# sterownik_RC.net
KiCad netlist of a schematic drawn in EAGLE
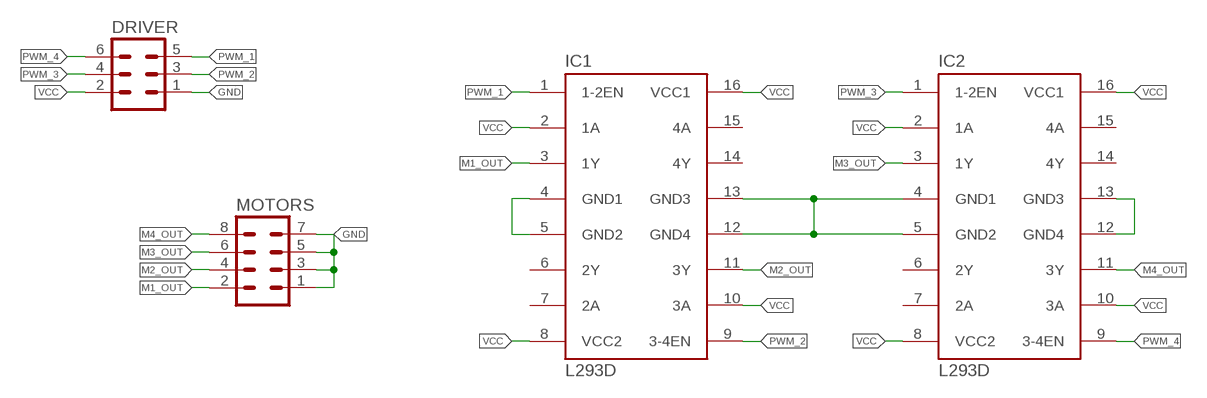
[diagram p0: schematic, sheet 1]

(export (version "E")
  (design (tool "Eeschema 10.0.6"))
  (components
    (comp (ref "DRIVER")
      (value "MA03-2")
      (footprint "eagle-import:MA03-2")
      (libsource (lib "eagle-import") (part "MA03-2"))
    )
    (comp (ref "IC1")
      (value "L293D")
      (footprint "eagle-import:DIL16")
      (libsource (lib "eagle-import") (part "L293D"))
    )
    (comp (ref "IC2")
      (value "L293D")
      (footprint "eagle-import:DIL16")
      (libsource (lib "eagle-import") (part "L293D"))
    )
    (comp (ref "MOTORS")
      (value "MA04-2")
      (footprint "eagle-import:MA04-2")
      (libsource (lib "eagle-import") (part "MA04-2"))
    )
  )
  (nets
    (net (code "1") (name "GND") (class "Default")
      (node (ref "DRIVER") (pin "1") (pinfunction "1_1") (pintype "passive"))
      (node (ref "IC1") (pin "12") (pinfunction "GND4_12") (pintype "power_in"))
      (node (ref "IC1") (pin "13") (pinfunction "GND3_13") (pintype "power_in"))
      (node (ref "IC1") (pin "4") (pinfunction "GND1_4") (pintype "power_in"))
      (node (ref "IC1") (pin "5") (pinfunction "GND2_5") (pintype "power_in"))
      (node (ref "IC2") (pin "12") (pinfunction "GND4_12") (pintype "power_in"))
      (node (ref "IC2") (pin "13") (pinfunction "GND3_13") (pintype "power_in"))
      (node (ref "IC2") (pin "4") (pinfunction "GND1_4") (pintype "power_in"))
      (node (ref "IC2") (pin "5") (pinfunction "GND2_5") (pintype "power_in"))
      (node (ref "MOTORS") (pin "1") (pinfunction "1_1") (pintype "passive"))
      (node (ref "MOTORS") (pin "3") (pinfunction "3_3") (pintype "passive"))
      (node (ref "MOTORS") (pin "5") (pinfunction "5_5") (pintype "passive"))
      (node (ref "MOTORS") (pin "7") (pinfunction "7_7") (pintype "passive"))
    )
    (net (code "2") (name "M1_OUT") (class "Default")
      (node (ref "IC1") (pin "3") (pinfunction "1Y_3") (pintype "output"))
      (node (ref "MOTORS") (pin "2") (pinfunction "2_2") (pintype "passive"))
    )
    (net (code "3") (name "M2_OUT") (class "Default")
      (node (ref "IC1") (pin "11") (pinfunction "3Y_11") (pintype "output"))
      (node (ref "MOTORS") (pin "4") (pinfunction "4_4") (pintype "passive"))
    )
    (net (code "4") (name "M3_OUT") (class "Default")
      (node (ref "IC2") (pin "3") (pinfunction "1Y_3") (pintype "output"))
      (node (ref "MOTORS") (pin "6") (pinfunction "6_6") (pintype "passive"))
    )
    (net (code "5") (name "M4_OUT") (class "Default")
      (node (ref "IC2") (pin "11") (pinfunction "3Y_11") (pintype "output"))
      (node (ref "MOTORS") (pin "8") (pinfunction "8_8") (pintype "passive"))
    )
    (net (code "6") (name "PWM_1") (class "Default")
      (node (ref "DRIVER") (pin "5") (pinfunction "5_5") (pintype "passive"))
      (node (ref "IC1") (pin "1") (pinfunction "1-2EN_1") (pintype "input"))
    )
    (net (code "7") (name "PWM_2") (class "Default")
      (node (ref "DRIVER") (pin "3") (pinfunction "3_3") (pintype "passive"))
      (node (ref "IC1") (pin "9") (pinfunction "3-4EN_9") (pintype "input"))
    )
    (net (code "8") (name "PWM_3") (class "Default")
      (node (ref "DRIVER") (pin "4") (pinfunction "4_4") (pintype "passive"))
      (node (ref "IC2") (pin "1") (pinfunction "1-2EN_1") (pintype "input"))
    )
    (net (code "9") (name "PWM_4") (class "Default")
      (node (ref "DRIVER") (pin "6") (pinfunction "6_6") (pintype "passive"))
      (node (ref "IC2") (pin "9") (pinfunction "3-4EN_9") (pintype "input"))
    )
    (net (code "10") (name "VCC") (class "Default")
      (node (ref "DRIVER") (pin "2") (pinfunction "2_2") (pintype "passive"))
      (node (ref "IC1") (pin "10") (pinfunction "3A_10") (pintype "input"))
      (node (ref "IC1") (pin "16") (pinfunction "VCC1_16") (pintype "power_in"))
      (node (ref "IC1") (pin "2") (pinfunction "1A_2") (pintype "input"))
      (node (ref "IC1") (pin "8") (pinfunction "VCC2_8") (pintype "power_in"))
      (node (ref "IC2") (pin "10") (pinfunction "3A_10") (pintype "input"))
      (node (ref "IC2") (pin "16") (pinfunction "VCC1_16") (pintype "power_in"))
      (node (ref "IC2") (pin "2") (pinfunction "1A_2") (pintype "input"))
      (node (ref "IC2") (pin "8") (pinfunction "VCC2_8") (pintype "power_in"))
    )
    (net (code "11") (name "unconnected-(IC1-2A-Pad7)") (class "Default")
      (node (ref "IC1") (pin "7") (pinfunction "2A_7") (pintype "input"))
    )
    (net (code "12") (name "unconnected-(IC1-2Y-Pad6)") (class "Default")
      (node (ref "IC1") (pin "6") (pinfunction "2Y_6") (pintype "output"))
    )
    (net (code "13") (name "unconnected-(IC1-4A-Pad15)") (class "Default")
      (node (ref "IC1") (pin "15") (pinfunction "4A_15") (pintype "input"))
    )
    (net (code "14") (name "unconnected-(IC1-4Y-Pad14)") (class "Default")
      (node (ref "IC1") (pin "14") (pinfunction "4Y_14") (pintype "output"))
    )
    (net (code "15") (name "unconnected-(IC2-2A-Pad7)") (class "Default")
      (node (ref "IC2") (pin "7") (pinfunction "2A_7") (pintype "input"))
    )
    (net (code "16") (name "unconnected-(IC2-2Y-Pad6)") (class "Default")
      (node (ref "IC2") (pin "6") (pinfunction "2Y_6") (pintype "output"))
    )
    (net (code "17") (name "unconnected-(IC2-4A-Pad15)") (class "Default")
      (node (ref "IC2") (pin "15") (pinfunction "4A_15") (pintype "input"))
    )
    (net (code "18") (name "unconnected-(IC2-4Y-Pad14)") (class "Default")
      (node (ref "IC2") (pin "14") (pinfunction "4Y_14") (pintype "output"))
    )
  )
)
